# VDU_TMS_final_rev01.net
KiCad netlist of a schematic drawn in EAGLE
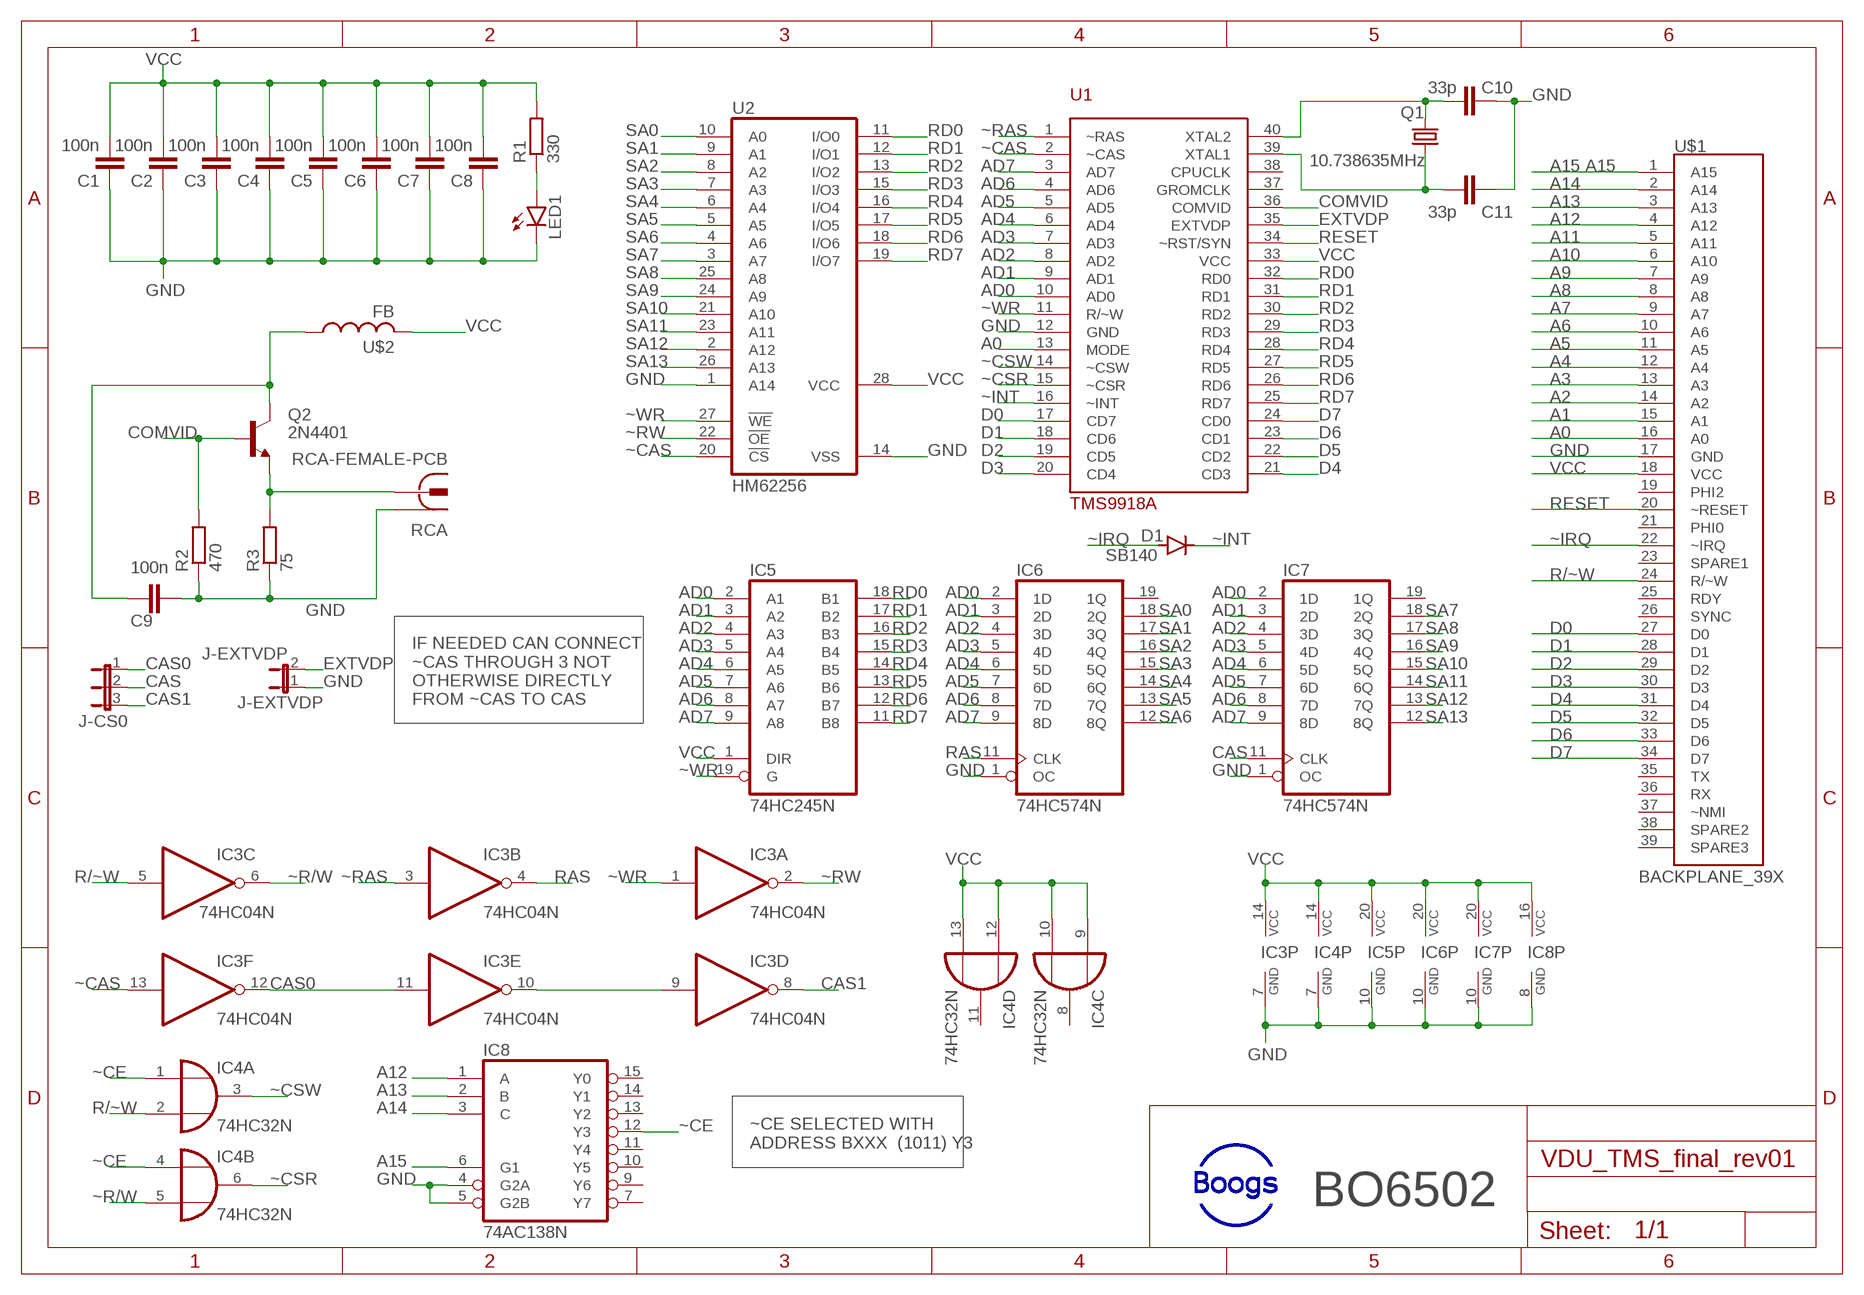
[diagram p0: schematic, sheet 1]

(export (version "E")
  (design (tool "Eeschema 10.0.6"))
  (components
    (comp (ref "C1")
      (value "100n")
      (footprint "eagle-import:C025-025X050")
      (libsource (lib "eagle-import") (part "C-EU025-025X050"))
    )
    (comp (ref "C2")
      (value "100n")
      (footprint "eagle-import:C025-025X050")
      (libsource (lib "eagle-import") (part "C-EU025-025X050"))
    )
    (comp (ref "C3")
      (value "100n")
      (footprint "eagle-import:C025-025X050")
      (libsource (lib "eagle-import") (part "C-EU025-025X050"))
    )
    (comp (ref "C4")
      (value "100n")
      (footprint "eagle-import:C025-025X050")
      (libsource (lib "eagle-import") (part "C-EU025-025X050"))
    )
    (comp (ref "C5")
      (value "100n")
      (footprint "eagle-import:C025-025X050")
      (libsource (lib "eagle-import") (part "C-EU025-025X050"))
    )
    (comp (ref "C6")
      (value "100n")
      (footprint "eagle-import:C025-025X050")
      (libsource (lib "eagle-import") (part "C-EU025-025X050"))
    )
    (comp (ref "C7")
      (value "100n")
      (footprint "eagle-import:C025-025X050")
      (libsource (lib "eagle-import") (part "C-EU025-025X050"))
    )
    (comp (ref "C8")
      (value "100n")
      (footprint "eagle-import:C025-025X050")
      (libsource (lib "eagle-import") (part "C-EU025-025X050"))
    )
    (comp (ref "C9")
      (value "100n")
      (footprint "eagle-import:C025-025X050")
      (libsource (lib "eagle-import") (part "C-EU025-025X050"))
    )
    (comp (ref "C10")
      (value "33p")
      (footprint "eagle-import:C025-025X050")
      (libsource (lib "eagle-import") (part "C-EU025-025X050"))
    )
    (comp (ref "C11")
      (value "33p")
      (footprint "eagle-import:C025-025X050")
      (libsource (lib "eagle-import") (part "C-EU025-025X050"))
    )
    (comp (ref "D1")
      (value "SB140")
      (footprint "eagle-import:DO41-10")
      (libsource (lib "eagle-import") (part "1N4004"))
    )
    (comp (ref "IC3")
      (value "74HC04N")
      (footprint "eagle-import:DIL14")
      (libsource (lib "eagle-import") (part "7404NHC"))
    )
    (comp (ref "IC4")
      (value "74HC32N")
      (footprint "eagle-import:DIL14")
      (libsource (lib "eagle-import") (part "7432NHC"))
    )
    (comp (ref "IC5")
      (value "74HC245N")
      (footprint "eagle-import:DIL20")
      (libsource (lib "eagle-import") (part "74245NHC"))
    )
    (comp (ref "IC6")
      (value "74HC574N")
      (footprint "eagle-import:DIL20")
      (libsource (lib "eagle-import") (part "74574NHC"))
    )
    (comp (ref "IC7")
      (value "74HC574N")
      (footprint "eagle-import:DIL20")
      (libsource (lib "eagle-import") (part "74574NHC"))
    )
    (comp (ref "IC8")
      (value "74AC138N")
      (footprint "eagle-import:DIL16")
      (libsource (lib "eagle-import") (part "74138NAC"))
    )
    (comp (ref "J-CAS")
      (value "J-CS0")
      (footprint "eagle-import:JP2")
      (libsource (lib "eagle-import") (part "JP2E"))
    )
    (comp (ref "J-EXTVDP")
      (value "J-EXTVDP")
      (footprint "eagle-import:JP1")
      (libsource (lib "eagle-import") (part "JP1E"))
    )
    (comp (ref "LED1")
      (value "RED")
      (footprint "eagle-import:LED5MM")
      (libsource (lib "eagle-import") (part "LED5MM"))
    )
    (comp (ref "Q1")
      (value "10.738635MHz")
      (footprint "eagle-import:HC49_S")
      (libsource (lib "eagle-import") (part "CRYSTALHC49S"))
    )
    (comp (ref "Q2")
      (value "2N4401")
      (footprint "eagle-import:TO92-EBC")
      (libsource (lib "eagle-import") (part "-NPN-TO92-EBC"))
    )
    (comp (ref "R1")
      (value "330")
      (footprint "eagle-import:0207_10")
      (libsource (lib "eagle-import") (part "R-EU_0207/10"))
    )
    (comp (ref "R2")
      (value "470")
      (footprint "eagle-import:0207_10")
      (libsource (lib "eagle-import") (part "R-EU_0207/10"))
    )
    (comp (ref "R3")
      (value "75")
      (footprint "eagle-import:0207_10")
      (libsource (lib "eagle-import") (part "R-EU_0207/10"))
    )
    (comp (ref "RCA")
      (value "RCA-FEMALE-PCB")
      (footprint "eagle-import:RCA-FEMALE-PCB")
      (libsource (lib "eagle-import") (part "RCA-FEMALE-PCB"))
    )
    (comp (ref "U$1")
      (value "BACKPLANE_39X")
      (footprint "eagle-import:BP_39X")
      (fields (field (name "A15") "A15"))
      (libsource (lib "eagle-import") (part "BACKPLANE_39X"))
    )
    (comp (ref "U$2") (value "FB") (footprint "eagle-import:FB") (libsource (lib "eagle-import") (part "FB")))
    (comp (ref "U1")
      (value "TMS9918A")
      (footprint "eagle-import:DIL40")
      (libsource (lib "eagle-import") (part "TMS9918A"))
    )
    (comp (ref "U2")
      (value "HM62256")
      (footprint "eagle-import:DIL28-6")
      (libsource (lib "eagle-import") (part "62256P"))
    )
  )
  (nets
    (net (code "1") (name "/A0") (class "Default")
      (node (ref "U$1") (pin "16") (pinfunction "A0_16") (pintype "bidirectional"))
      (node (ref "U1") (pin "13") (pinfunction "MODE_13") (pintype "bidirectional"))
    )
    (net (code "2") (name "/A1") (class "Default")
      (node (ref "U$1") (pin "15") (pinfunction "A1_15") (pintype "bidirectional"))
    )
    (net (code "3") (name "/A2") (class "Default")
      (node (ref "U$1") (pin "14") (pinfunction "A2_14") (pintype "bidirectional"))
    )
    (net (code "4") (name "/A3") (class "Default")
      (node (ref "U$1") (pin "13") (pinfunction "A3_13") (pintype "bidirectional"))
    )
    (net (code "5") (name "/A4") (class "Default")
      (node (ref "U$1") (pin "12") (pinfunction "A4_12") (pintype "bidirectional"))
    )
    (net (code "6") (name "/A5") (class "Default")
      (node (ref "U$1") (pin "11") (pinfunction "A5_11") (pintype "bidirectional"))
    )
    (net (code "7") (name "/A6") (class "Default")
      (node (ref "U$1") (pin "10") (pinfunction "A6_10") (pintype "bidirectional"))
    )
    (net (code "8") (name "/A7") (class "Default")
      (node (ref "U$1") (pin "9") (pinfunction "A7_9") (pintype "bidirectional"))
    )
    (net (code "9") (name "/A8") (class "Default")
      (node (ref "U$1") (pin "8") (pinfunction "A8_8") (pintype "bidirectional"))
    )
    (net (code "10") (name "/A9") (class "Default")
      (node (ref "U$1") (pin "7") (pinfunction "A9_7") (pintype "bidirectional"))
    )
    (net (code "11") (name "/A10") (class "Default")
      (node (ref "U$1") (pin "6") (pinfunction "A10_6") (pintype "bidirectional"))
    )
    (net (code "12") (name "/A11") (class "Default")
      (node (ref "U$1") (pin "5") (pinfunction "A11_5") (pintype "bidirectional"))
    )
    (net (code "13") (name "/A12") (class "Default")
      (node (ref "IC8") (pin "1") (pinfunction "A_1") (pintype "input"))
      (node (ref "U$1") (pin "4") (pinfunction "A12_4") (pintype "bidirectional"))
    )
    (net (code "14") (name "/A13") (class "Default")
      (node (ref "IC8") (pin "2") (pinfunction "B_2") (pintype "input"))
      (node (ref "U$1") (pin "3") (pinfunction "A13_3") (pintype "bidirectional"))
    )
    (net (code "15") (name "/A14") (class "Default")
      (node (ref "IC8") (pin "3") (pinfunction "C_3") (pintype "input"))
      (node (ref "U$1") (pin "2") (pinfunction "A14_2") (pintype "bidirectional"))
    )
    (net (code "16") (name "/A15") (class "Default")
      (node (ref "IC8") (pin "6") (pinfunction "G1_6") (pintype "input"))
      (node (ref "U$1") (pin "1") (pinfunction "A15_1") (pintype "bidirectional"))
    )
    (net (code "17") (name "/AD0") (class "Default")
      (node (ref "IC5") (pin "2") (pinfunction "A1_2") (pintype "bidirectional"))
      (node (ref "IC6") (pin "2") (pinfunction "1D_2") (pintype "input"))
      (node (ref "IC7") (pin "2") (pinfunction "1D_2") (pintype "input"))
      (node (ref "U1") (pin "10") (pinfunction "AD0_10") (pintype "bidirectional"))
    )
    (net (code "18") (name "/AD1") (class "Default")
      (node (ref "IC5") (pin "3") (pinfunction "A2_3") (pintype "bidirectional"))
      (node (ref "IC6") (pin "3") (pinfunction "2D_3") (pintype "input"))
      (node (ref "IC7") (pin "3") (pinfunction "2D_3") (pintype "input"))
      (node (ref "U1") (pin "9") (pinfunction "AD1_9") (pintype "bidirectional"))
    )
    (net (code "19") (name "/AD2") (class "Default")
      (node (ref "IC5") (pin "4") (pinfunction "A3_4") (pintype "bidirectional"))
      (node (ref "IC6") (pin "4") (pinfunction "3D_4") (pintype "input"))
      (node (ref "IC7") (pin "4") (pinfunction "3D_4") (pintype "input"))
      (node (ref "U1") (pin "8") (pinfunction "AD2_8") (pintype "bidirectional"))
    )
    (net (code "20") (name "/AD3") (class "Default")
      (node (ref "IC5") (pin "5") (pinfunction "A4_5") (pintype "bidirectional"))
      (node (ref "IC6") (pin "5") (pinfunction "4D_5") (pintype "input"))
      (node (ref "IC7") (pin "5") (pinfunction "4D_5") (pintype "input"))
      (node (ref "U1") (pin "7") (pinfunction "AD3_7") (pintype "input"))
    )
    (net (code "21") (name "/AD4") (class "Default")
      (node (ref "IC5") (pin "6") (pinfunction "A5_6") (pintype "bidirectional"))
      (node (ref "IC6") (pin "6") (pinfunction "5D_6") (pintype "input"))
      (node (ref "IC7") (pin "6") (pinfunction "5D_6") (pintype "input"))
      (node (ref "U1") (pin "6") (pinfunction "AD4_6") (pintype "bidirectional"))
    )
    (net (code "22") (name "/AD5") (class "Default")
      (node (ref "IC5") (pin "7") (pinfunction "A6_7") (pintype "bidirectional"))
      (node (ref "IC6") (pin "7") (pinfunction "6D_7") (pintype "input"))
      (node (ref "IC7") (pin "7") (pinfunction "6D_7") (pintype "input"))
      (node (ref "U1") (pin "5") (pinfunction "AD5_5") (pintype "bidirectional"))
    )
    (net (code "23") (name "/AD6") (class "Default")
      (node (ref "IC5") (pin "8") (pinfunction "A7_8") (pintype "bidirectional"))
      (node (ref "IC6") (pin "8") (pinfunction "7D_8") (pintype "input"))
      (node (ref "IC7") (pin "8") (pinfunction "7D_8") (pintype "input"))
      (node (ref "U1") (pin "4") (pinfunction "AD6_4") (pintype "bidirectional"))
    )
    (net (code "24") (name "/AD7") (class "Default")
      (node (ref "IC5") (pin "9") (pinfunction "A8_9") (pintype "bidirectional"))
      (node (ref "IC6") (pin "9") (pinfunction "8D_9") (pintype "input"))
      (node (ref "IC7") (pin "9") (pinfunction "8D_9") (pintype "input"))
      (node (ref "U1") (pin "3") (pinfunction "AD7_3") (pintype "bidirectional"))
    )
    (net (code "25") (name "/CAS") (class "Default")
      (node (ref "IC7") (pin "11") (pinfunction "CLK_11") (pintype "input"))
      (node (ref "J-CAS") (pin "2") (pinfunction "2_2") (pintype "passive"))
    )
    (net (code "26") (name "/CAS0") (class "Default")
      (node (ref "IC3") (pin "11") (pinfunction "I_11") (pintype "input"))
      (node (ref "IC3") (pin "12") (pinfunction "O_12") (pintype "output"))
      (node (ref "J-CAS") (pin "1") (pinfunction "1_1") (pintype "passive"))
    )
    (net (code "27") (name "/CAS1") (class "Default")
      (node (ref "IC3") (pin "8") (pinfunction "O_8") (pintype "output"))
      (node (ref "J-CAS") (pin "3") (pinfunction "3_3") (pintype "passive"))
    )
    (net (code "28") (name "/COMVID") (class "Default")
      (node (ref "Q2") (pin "B") (pinfunction "B_B") (pintype "passive"))
      (node (ref "R2") (pin "2") (pinfunction "2_2") (pintype "passive"))
      (node (ref "U1") (pin "36") (pinfunction "COMVID_36") (pintype "bidirectional"))
    )
    (net (code "29") (name "/D0") (class "Default")
      (node (ref "U$1") (pin "27") (pinfunction "D0_27") (pintype "bidirectional"))
      (node (ref "U1") (pin "17") (pinfunction "CD7_17") (pintype "bidirectional"))
    )
    (net (code "30") (name "/D1") (class "Default")
      (node (ref "U$1") (pin "28") (pinfunction "D1_28") (pintype "bidirectional"))
      (node (ref "U1") (pin "18") (pinfunction "CD6_18") (pintype "bidirectional"))
    )
    (net (code "31") (name "/D2") (class "Default")
      (node (ref "U$1") (pin "29") (pinfunction "D2_29") (pintype "bidirectional"))
      (node (ref "U1") (pin "19") (pinfunction "CD5_19") (pintype "bidirectional"))
    )
    (net (code "32") (name "/D3") (class "Default")
      (node (ref "U$1") (pin "30") (pinfunction "D3_30") (pintype "bidirectional"))
      (node (ref "U1") (pin "20") (pinfunction "CD4_20") (pintype "bidirectional"))
    )
    (net (code "33") (name "/D4") (class "Default")
      (node (ref "U$1") (pin "31") (pinfunction "D4_31") (pintype "bidirectional"))
      (node (ref "U1") (pin "21") (pinfunction "CD3_21") (pintype "bidirectional"))
    )
    (net (code "34") (name "/D5") (class "Default")
      (node (ref "U$1") (pin "32") (pinfunction "D5_32") (pintype "bidirectional"))
      (node (ref "U1") (pin "22") (pinfunction "CD2_22") (pintype "bidirectional"))
    )
    (net (code "35") (name "/D6") (class "Default")
      (node (ref "U$1") (pin "33") (pinfunction "D6_33") (pintype "bidirectional"))
      (node (ref "U1") (pin "23") (pinfunction "CD1_23") (pintype "bidirectional"))
    )
    (net (code "36") (name "/D7") (class "Default")
      (node (ref "U$1") (pin "34") (pinfunction "D7_34") (pintype "bidirectional"))
      (node (ref "U1") (pin "24") (pinfunction "CD0_24") (pintype "bidirectional"))
    )
    (net (code "37") (name "/EXTVDP") (class "Default")
      (node (ref "J-EXTVDP") (pin "2") (pinfunction "2_2") (pintype "passive"))
      (node (ref "U1") (pin "35") (pinfunction "EXTVDP_35") (pintype "bidirectional"))
    )
    (net (code "38") (name "/GND") (class "Default")
      (node (ref "C1") (pin "1") (pinfunction "1_1") (pintype "passive"))
      (node (ref "C10") (pin "1") (pinfunction "1_1") (pintype "passive"))
      (node (ref "C11") (pin "1") (pinfunction "1_1") (pintype "passive"))
      (node (ref "C2") (pin "1") (pinfunction "1_1") (pintype "passive"))
      (node (ref "C3") (pin "1") (pinfunction "1_1") (pintype "passive"))
      (node (ref "C4") (pin "1") (pinfunction "1_1") (pintype "passive"))
      (node (ref "C5") (pin "1") (pinfunction "1_1") (pintype "passive"))
      (node (ref "C6") (pin "1") (pinfunction "1_1") (pintype "passive"))
      (node (ref "C7") (pin "1") (pinfunction "1_1") (pintype "passive"))
      (node (ref "C8") (pin "1") (pinfunction "1_1") (pintype "passive"))
      (node (ref "C9") (pin "1") (pinfunction "1_1") (pintype "passive"))
      (node (ref "IC3") (pin "7") (pinfunction "GND_7") (pintype "power_in"))
      (node (ref "IC4") (pin "7") (pinfunction "GND_7") (pintype "power_in"))
      (node (ref "IC5") (pin "10") (pinfunction "GND_10") (pintype "power_in"))
      (node (ref "IC6") (pin "1") (pinfunction "OC_1") (pintype "input"))
      (node (ref "IC6") (pin "10") (pinfunction "GND_10") (pintype "power_in"))
      (node (ref "IC7") (pin "1") (pinfunction "OC_1") (pintype "input"))
      (node (ref "IC7") (pin "10") (pinfunction "GND_10") (pintype "power_in"))
      (node (ref "IC8") (pin "4") (pinfunction "G2A_4") (pintype "input"))
      (node (ref "IC8") (pin "5") (pinfunction "G2B_5") (pintype "input"))
      (node (ref "IC8") (pin "8") (pinfunction "GND_8") (pintype "power_in"))
      (node (ref "J-EXTVDP") (pin "1") (pinfunction "1_1") (pintype "passive"))
      (node (ref "LED1") (pin "K") (pinfunction "C_K") (pintype "passive"))
      (node (ref "R2") (pin "1") (pinfunction "1_1") (pintype "passive"))
      (node (ref "R3") (pin "1") (pinfunction "1_1") (pintype "passive"))
      (node (ref "RCA") (pin "1") (pinfunction "1_1") (pintype "passive"))
      (node (ref "U$1") (pin "17") (pinfunction "GND_17") (pintype "bidirectional"))
      (node (ref "U1") (pin "12") (pinfunction "GND_12") (pintype "power_in"))
      (node (ref "U2") (pin "1") (pinfunction "A14_1") (pintype "input"))
      (node (ref "U2") (pin "14") (pinfunction "VSS_14") (pintype "power_in"))
    )
    (net (code "39") (name "/RAS") (class "Default")
      (node (ref "IC3") (pin "4") (pinfunction "O_4") (pintype "output"))
      (node (ref "IC6") (pin "11") (pinfunction "CLK_11") (pintype "input"))
    )
    (net (code "40") (name "/RD0") (class "Default")
      (node (ref "IC5") (pin "18") (pinfunction "B1_18") (pintype "bidirectional"))
      (node (ref "U1") (pin "32") (pinfunction "RD0_32") (pintype "bidirectional"))
      (node (ref "U2") (pin "11") (pinfunction "I/O0_11") (pintype "bidirectional"))
    )
    (net (code "41") (name "/RD1") (class "Default")
      (node (ref "IC5") (pin "17") (pinfunction "B2_17") (pintype "bidirectional"))
      (node (ref "U1") (pin "31") (pinfunction "RD1_31") (pintype "bidirectional"))
      (node (ref "U2") (pin "12") (pinfunction "I/O1_12") (pintype "bidirectional"))
    )
    (net (code "42") (name "/RD2") (class "Default")
      (node (ref "IC5") (pin "16") (pinfunction "B3_16") (pintype "bidirectional"))
      (node (ref "U1") (pin "30") (pinfunction "RD2_30") (pintype "bidirectional"))
      (node (ref "U2") (pin "13") (pinfunction "I/O2_13") (pintype "bidirectional"))
    )
    (net (code "43") (name "/RD3") (class "Default")
      (node (ref "IC5") (pin "15") (pinfunction "B4_15") (pintype "bidirectional"))
      (node (ref "U1") (pin "29") (pinfunction "RD3_29") (pintype "bidirectional"))
      (node (ref "U2") (pin "15") (pinfunction "I/O3_15") (pintype "bidirectional"))
    )
    (net (code "44") (name "/RD4") (class "Default")
      (node (ref "IC5") (pin "14") (pinfunction "B5_14") (pintype "bidirectional"))
      (node (ref "U1") (pin "28") (pinfunction "RD4_28") (pintype "bidirectional"))
      (node (ref "U2") (pin "16") (pinfunction "I/O4_16") (pintype "bidirectional"))
    )
    (net (code "45") (name "/RD5") (class "Default")
      (node (ref "IC5") (pin "13") (pinfunction "B6_13") (pintype "bidirectional"))
      (node (ref "U1") (pin "27") (pinfunction "RD5_27") (pintype "bidirectional"))
      (node (ref "U2") (pin "17") (pinfunction "I/O5_17") (pintype "bidirectional"))
    )
    (net (code "46") (name "/RD6") (class "Default")
      (node (ref "IC5") (pin "12") (pinfunction "B7_12") (pintype "bidirectional"))
      (node (ref "U1") (pin "26") (pinfunction "RD6_26") (pintype "bidirectional"))
      (node (ref "U2") (pin "18") (pinfunction "I/O6_18") (pintype "bidirectional"))
    )
    (net (code "47") (name "/RD7") (class "Default")
      (node (ref "IC5") (pin "11") (pinfunction "B8_11") (pintype "bidirectional"))
      (node (ref "U1") (pin "25") (pinfunction "RD7_25") (pintype "bidirectional"))
      (node (ref "U2") (pin "19") (pinfunction "I/O7_19") (pintype "bidirectional"))
    )
    (net (code "48") (name "/RESET") (class "Default")
      (node (ref "U$1") (pin "20") (pinfunction "~{RESET}_20") (pintype "bidirectional"))
      (node (ref "U1") (pin "34") (pinfunction "~{RST/SYN}_34") (pintype "bidirectional"))
    )
    (net (code "49") (name "/R{slash}~{W}") (class "Default")
      (node (ref "IC3") (pin "5") (pinfunction "I_5") (pintype "input"))
      (node (ref "IC4") (pin "2") (pinfunction "I1_2") (pintype "input"))
      (node (ref "U$1") (pin "24") (pinfunction "R/~{W}_24") (pintype "bidirectional"))
    )
    (net (code "50") (name "/SA0") (class "Default")
      (node (ref "IC6") (pin "18") (pinfunction "2Q_18") (pintype "tri_state"))
      (node (ref "U2") (pin "10") (pinfunction "A0_10") (pintype "input"))
    )
    (net (code "51") (name "/SA1") (class "Default")
      (node (ref "IC6") (pin "17") (pinfunction "3Q_17") (pintype "tri_state"))
      (node (ref "U2") (pin "9") (pinfunction "A1_9") (pintype "input"))
    )
    (net (code "52") (name "/SA2") (class "Default")
      (node (ref "IC6") (pin "16") (pinfunction "4Q_16") (pintype "tri_state"))
      (node (ref "U2") (pin "8") (pinfunction "A2_8") (pintype "input"))
    )
    (net (code "53") (name "/SA3") (class "Default")
      (node (ref "IC6") (pin "15") (pinfunction "5Q_15") (pintype "tri_state"))
      (node (ref "U2") (pin "7") (pinfunction "A3_7") (pintype "input"))
    )
    (net (code "54") (name "/SA4") (class "Default")
      (node (ref "IC6") (pin "14") (pinfunction "6Q_14") (pintype "tri_state"))
      (node (ref "U2") (pin "6") (pinfunction "A4_6") (pintype "input"))
    )
    (net (code "55") (name "/SA5") (class "Default")
      (node (ref "IC6") (pin "13") (pinfunction "7Q_13") (pintype "tri_state"))
      (node (ref "U2") (pin "5") (pinfunction "A5_5") (pintype "input"))
    )
    (net (code "56") (name "/SA6") (class "Default")
      (node (ref "IC6") (pin "12") (pinfunction "8Q_12") (pintype "tri_state"))
      (node (ref "U2") (pin "4") (pinfunction "A6_4") (pintype "input"))
    )
    (net (code "57") (name "/SA7") (class "Default")
      (node (ref "IC7") (pin "18") (pinfunction "2Q_18") (pintype "tri_state"))
      (node (ref "U2") (pin "3") (pinfunction "A7_3") (pintype "input"))
    )
    (net (code "58") (name "/SA8") (class "Default")
      (node (ref "IC7") (pin "17") (pinfunction "3Q_17") (pintype "tri_state"))
      (node (ref "U2") (pin "25") (pinfunction "A8_25") (pintype "input"))
    )
    (net (code "59") (name "/SA9") (class "Default")
      (node (ref "IC7") (pin "16") (pinfunction "4Q_16") (pintype "tri_state"))
      (node (ref "U2") (pin "24") (pinfunction "A9_24") (pintype "input"))
    )
    (net (code "60") (name "/SA10") (class "Default")
      (node (ref "IC7") (pin "15") (pinfunction "5Q_15") (pintype "tri_state"))
      (node (ref "U2") (pin "21") (pinfunction "A10_21") (pintype "input"))
    )
    (net (code "61") (name "/SA11") (class "Default")
      (node (ref "IC7") (pin "14") (pinfunction "6Q_14") (pintype "tri_state"))
      (node (ref "U2") (pin "23") (pinfunction "A11_23") (pintype "input"))
    )
    (net (code "62") (name "/SA12") (class "Default")
      (node (ref "IC7") (pin "13") (pinfunction "7Q_13") (pintype "tri_state"))
      (node (ref "U2") (pin "2") (pinfunction "A12_2") (pintype "input"))
    )
    (net (code "63") (name "/SA13") (class "Default")
      (node (ref "IC7") (pin "12") (pinfunction "8Q_12") (pintype "tri_state"))
      (node (ref "U2") (pin "26") (pinfunction "A13_26") (pintype "input"))
    )
    (net (code "64") (name "/VCC") (class "Default")
      (node (ref "C1") (pin "2") (pinfunction "2_2") (pintype "passive"))
      (node (ref "C2") (pin "2") (pinfunction "2_2") (pintype "passive"))
      (node (ref "C3") (pin "2") (pinfunction "2_2") (pintype "passive"))
      (node (ref "C4") (pin "2") (pinfunction "2_2") (pintype "passive"))
      (node (ref "C5") (pin "2") (pinfunction "2_2") (pintype "passive"))
      (node (ref "C6") (pin "2") (pinfunction "2_2") (pintype "passive"))
      (node (ref "C7") (pin "2") (pinfunction "2_2") (pintype "passive"))
      (node (ref "C8") (pin "2") (pinfunction "2_2") (pintype "passive"))
      (node (ref "IC3") (pin "14") (pinfunction "VCC_14") (pintype "power_in"))
      (node (ref "IC4") (pin "10") (pinfunction "I1_10") (pintype "input"))
      (node (ref "IC4") (pin "12") (pinfunction "I0_12") (pintype "input"))
      (node (ref "IC4") (pin "13") (pinfunction "I1_13") (pintype "input"))
      (node (ref "IC4") (pin "14") (pinfunction "VCC_14") (pintype "power_in"))
      (node (ref "IC4") (pin "9") (pinfunction "I0_9") (pintype "input"))
      (node (ref "IC5") (pin "1") (pinfunction "DIR_1") (pintype "input"))
      (node (ref "IC5") (pin "20") (pinfunction "VCC_20") (pintype "power_in"))
      (node (ref "IC6") (pin "20") (pinfunction "VCC_20") (pintype "power_in"))
      (node (ref "IC7") (pin "20") (pinfunction "VCC_20") (pintype "power_in"))
      (node (ref "IC8") (pin "16") (pinfunction "VCC_16") (pintype "power_in"))
      (node (ref "R1") (pin "2") (pinfunction "2_2") (pintype "passive"))
      (node (ref "U$1") (pin "18") (pinfunction "VCC_18") (pintype "bidirectional"))
      (node (ref "U$2") (pin "P$2") (pinfunction "2_P$2") (pintype "passive"))
      (node (ref "U1") (pin "33") (pinfunction "VCC_33") (pintype "power_in"))
      (node (ref "U2") (pin "28") (pinfunction "VCC_28") (pintype "power_in"))
    )
    (net (code "65") (name "/~{CAS}") (class "Default")
      (node (ref "IC3") (pin "13") (pinfunction "I_13") (pintype "input"))
      (node (ref "U1") (pin "2") (pinfunction "~{CAS}_2") (pintype "bidirectional"))
      (node (ref "U2") (pin "20") (pinfunction "~{CS}_20") (pintype "input"))
    )
    (net (code "66") (name "/~{CE}") (class "Default")
      (node (ref "IC4") (pin "1") (pinfunction "I0_1") (pintype "input"))
      (node (ref "IC4") (pin "4") (pinfunction "I0_4") (pintype "input"))
      (node (ref "IC8") (pin "12") (pinfunction "Y3_12") (pintype "output"))
    )
    (net (code "67") (name "/~{CSR}") (class "Default")
      (node (ref "IC4") (pin "6") (pinfunction "O_6") (pintype "output"))
      (node (ref "U1") (pin "15") (pinfunction "~{CSR}_15") (pintype "bidirectional"))
    )
    (net (code "68") (name "/~{CSW}") (class "Default")
      (node (ref "IC4") (pin "3") (pinfunction "O_3") (pintype "output"))
      (node (ref "U1") (pin "14") (pinfunction "~{CSW}_14") (pintype "bidirectional"))
    )
    (net (code "69") (name "/~{INT}") (class "Default")
      (node (ref "D1") (pin "C") (pinfunction "C_C") (pintype "passive"))
      (node (ref "U1") (pin "16") (pinfunction "~{INT}_16") (pintype "bidirectional"))
    )
    (net (code "70") (name "/~{IRQ}") (class "Default")
      (node (ref "D1") (pin "A") (pinfunction "A_A") (pintype "passive"))
      (node (ref "U$1") (pin "22") (pinfunction "~{IRQ}_22") (pintype "bidirectional"))
    )
    (net (code "71") (name "/~{RAS}") (class "Default")
      (node (ref "IC3") (pin "3") (pinfunction "I_3") (pintype "input"))
      (node (ref "U1") (pin "1") (pinfunction "~{RAS}_1") (pintype "bidirectional"))
    )
    (net (code "72") (name "/~{RW}") (class "Default")
      (node (ref "IC3") (pin "2") (pinfunction "O_2") (pintype "output"))
      (node (ref "U2") (pin "22") (pinfunction "~{OE}_22") (pintype "input"))
    )
    (net (code "73") (name "/~{R{slash}W}") (class "Default")
      (node (ref "IC3") (pin "6") (pinfunction "O_6") (pintype "output"))
      (node (ref "IC4") (pin "5") (pinfunction "I1_5") (pintype "input"))
    )
    (net (code "74") (name "/~{WR}") (class "Default")
      (node (ref "IC3") (pin "1") (pinfunction "I_1") (pintype "input"))
      (node (ref "IC5") (pin "19") (pinfunction "G_19") (pintype "input"))
      (node (ref "U1") (pin "11") (pinfunction "R/~{W}_11") (pintype "bidirectional"))
      (node (ref "U2") (pin "27") (pinfunction "~{WE}_27") (pintype "input"))
    )
    (net (code "75") (name "Net-(IC3D-I)") (class "Default")
      (node (ref "IC3") (pin "10") (pinfunction "O_10") (pintype "output"))
      (node (ref "IC3") (pin "9") (pinfunction "I_9") (pintype "input"))
    )
    (net (code "76") (name "Net-(LED1-PadA)") (class "Default")
      (node (ref "LED1") (pin "A") (pinfunction "A_A") (pintype "passive"))
      (node (ref "R1") (pin "1") (pinfunction "1_1") (pintype "passive"))
    )
    (net (code "77") (name "Net-(Q2-PadE)") (class "Default")
      (node (ref "Q2") (pin "E") (pinfunction "E_E") (pintype "passive"))
      (node (ref "R3") (pin "2") (pinfunction "2_2") (pintype "passive"))
      (node (ref "RCA") (pin "2@1") (pinfunction "2_2@1") (pintype "passive"))
      (node (ref "RCA") (pin "2@2") (pinfunction "2_2@2") (pintype "passive"))
    )
    (net (code "78") (name "Net-(U$2-1)") (class "Default")
      (node (ref "C9") (pin "2") (pinfunction "2_2") (pintype "passive"))
      (node (ref "Q2") (pin "C") (pinfunction "C_C") (pintype "passive"))
      (node (ref "U$2") (pin "P$1") (pinfunction "1_P$1") (pintype "passive"))
    )
    (net (code "79") (name "Net-(U1-XTAL1)") (class "Default")
      (node (ref "C11") (pin "2") (pinfunction "2_2") (pintype "passive"))
      (node (ref "Q1") (pin "1") (pinfunction "1_1") (pintype "passive"))
      (node (ref "U1") (pin "39") (pinfunction "XTAL1_39") (pintype "bidirectional"))
    )
    (net (code "80") (name "Net-(U1-XTAL2)") (class "Default")
      (node (ref "C10") (pin "2") (pinfunction "2_2") (pintype "passive"))
      (node (ref "Q1") (pin "2") (pinfunction "2_2") (pintype "passive"))
      (node (ref "U1") (pin "40") (pinfunction "XTAL2_40") (pintype "bidirectional"))
    )
    (net (code "81") (name "unconnected-(IC4C-O-Pad8)") (class "Default")
      (node (ref "IC4") (pin "8") (pinfunction "O_8") (pintype "output"))
    )
    (net (code "82") (name "unconnected-(IC4D-O-Pad11)") (class "Default")
      (node (ref "IC4") (pin "11") (pinfunction "O_11") (pintype "output"))
    )
    (net (code "83") (name "unconnected-(IC6A-1Q-Pad19)") (class "Default")
      (node (ref "IC6") (pin "19") (pinfunction "1Q_19") (pintype "tri_state"))
    )
    (net (code "84") (name "unconnected-(IC7A-1Q-Pad19)") (class "Default")
      (node (ref "IC7") (pin "19") (pinfunction "1Q_19") (pintype "tri_state"))
    )
    (net (code "85") (name "unconnected-(IC8A-Y0-Pad15)") (class "Default")
      (node (ref "IC8") (pin "15") (pinfunction "Y0_15") (pintype "output"))
    )
    (net (code "86") (name "unconnected-(IC8A-Y1-Pad14)") (class "Default")
      (node (ref "IC8") (pin "14") (pinfunction "Y1_14") (pintype "output"))
    )
    (net (code "87") (name "unconnected-(IC8A-Y2-Pad13)") (class "Default")
      (node (ref "IC8") (pin "13") (pinfunction "Y2_13") (pintype "output"))
    )
    (net (code "88") (name "unconnected-(IC8A-Y4-Pad11)") (class "Default")
      (node (ref "IC8") (pin "11") (pinfunction "Y4_11") (pintype "output"))
    )
    (net (code "89") (name "unconnected-(IC8A-Y5-Pad10)") (class "Default")
      (node (ref "IC8") (pin "10") (pinfunction "Y5_10") (pintype "output"))
    )
    (net (code "90") (name "unconnected-(IC8A-Y6-Pad9)") (class "Default")
      (node (ref "IC8") (pin "9") (pinfunction "Y6_9") (pintype "output"))
    )
    (net (code "91") (name "unconnected-(IC8A-Y7-Pad7)") (class "Default")
      (node (ref "IC8") (pin "7") (pinfunction "Y7_7") (pintype "output"))
    )
    (net (code "92") (name "unconnected-(U$1-PHI0-Pad21)") (class "Default")
      (node (ref "U$1") (pin "21") (pinfunction "PHI0_21") (pintype "bidirectional"))
    )
    (net (code "93") (name "unconnected-(U$1-PHI2-Pad19)") (class "Default")
      (node (ref "U$1") (pin "19") (pinfunction "PHI2_19") (pintype "bidirectional"))
    )
    (net (code "94") (name "unconnected-(U$1-RDY-Pad25)") (class "Default")
      (node (ref "U$1") (pin "25") (pinfunction "RDY_25") (pintype "bidirectional"))
    )
    (net (code "95") (name "unconnected-(U$1-RX-Pad36)") (class "Default")
      (node (ref "U$1") (pin "36") (pinfunction "RX_36") (pintype "bidirectional"))
    )
    (net (code "96") (name "unconnected-(U$1-SPARE1-Pad23)") (class "Default")
      (node (ref "U$1") (pin "23") (pinfunction "SPARE1_23") (pintype "bidirectional"))
    )
    (net (code "97") (name "unconnected-(U$1-SPARE2-Pad38)") (class "Default")
      (node (ref "U$1") (pin "38") (pinfunction "SPARE2_38") (pintype "bidirectional"))
    )
    (net (code "98") (name "unconnected-(U$1-SPARE3-Pad39)") (class "Default")
      (node (ref "U$1") (pin "39") (pinfunction "SPARE3_39") (pintype "bidirectional"))
    )
    (net (code "99") (name "unconnected-(U$1-SYNC-Pad26)") (class "Default")
      (node (ref "U$1") (pin "26") (pinfunction "SYNC_26") (pintype "bidirectional"))
    )
    (net (code "100") (name "unconnected-(U$1-TX-Pad35)") (class "Default")
      (node (ref "U$1") (pin "35") (pinfunction "TX_35") (pintype "bidirectional"))
    )
    (net (code "101") (name "unconnected-(U$1-~{NMI}-Pad37)") (class "Default")
      (node (ref "U$1") (pin "37") (pinfunction "~{NMI}_37") (pintype "bidirectional"))
    )
    (net (code "102") (name "unconnected-(U1-CPUCLK-Pad38)") (class "Default")
      (node (ref "U1") (pin "38") (pinfunction "CPUCLK_38") (pintype "bidirectional"))
    )
    (net (code "103") (name "unconnected-(U1-GROMCLK-Pad37)") (class "Default")
      (node (ref "U1") (pin "37") (pinfunction "GROMCLK_37") (pintype "bidirectional"))
    )
  )
)
